# interface_smd.net
KiCad netlist of a schematic drawn in EAGLE
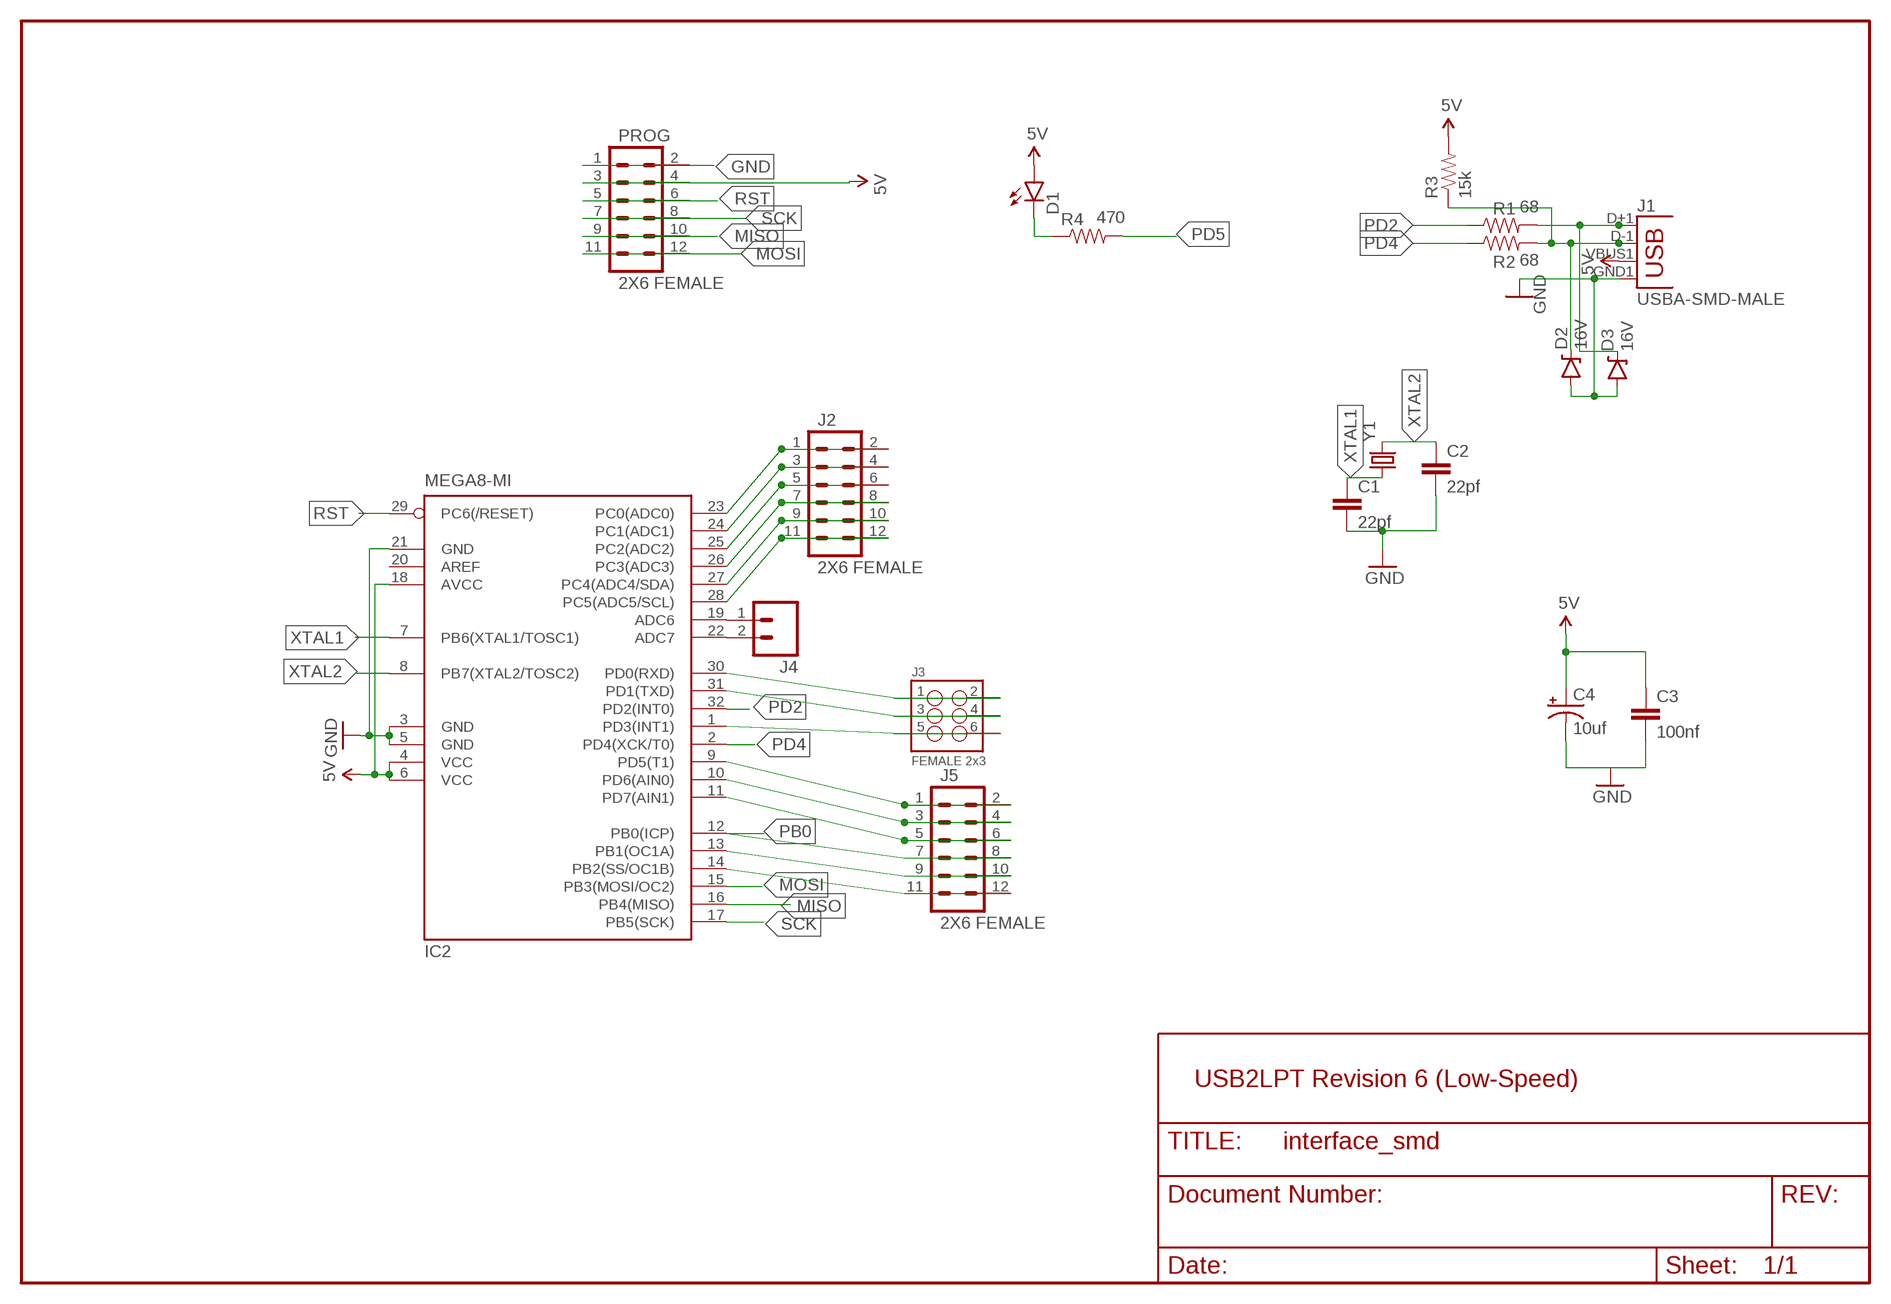
[diagram p0: schematic, sheet 1]

(export (version "E")
  (design (tool "Eeschema 10.0.6"))
  (components
    (comp (ref "C1")
      (value "22pf")
      (footprint "eagle-import:1206")
      (libsource (lib "eagle-import") (part "CAP1206"))
    )
    (comp (ref "C2")
      (value "22pf")
      (footprint "eagle-import:1206")
      (libsource (lib "eagle-import") (part "CAP1206"))
    )
    (comp (ref "C3")
      (value "100nf")
      (footprint "eagle-import:1206")
      (libsource (lib "eagle-import") (part "CAP1206"))
    )
    (comp (ref "C4")
      (value "10uf")
      (footprint "eagle-import:EIA3216")
      (libsource (lib "eagle-import") (part "CAP_POL1206"))
    )
    (comp (ref "D1")
      (value "LED1206")
      (footprint "eagle-import:LED-1206")
      (libsource (lib "eagle-import") (part "LED1206"))
    )
    (comp (ref "D2")
      (value "16V")
      (footprint "eagle-import:SOD-123")
      (libsource (lib "eagle-import") (part "DIODE-ZENER16V"))
    )
    (comp (ref "D3")
      (value "16V")
      (footprint "eagle-import:SOD-123")
      (libsource (lib "eagle-import") (part "DIODE-ZENER16V"))
    )
    (comp (ref "IC2")
      (value "MEGA8-MI")
      (footprint "eagle-import:MLF32")
      (fields (field (name "MPN") "ATMEGA88PA-MU"))
      (libsource (lib "eagle-import") (part "MEGA8-MI"))
    )
    (comp (ref "J1")
      (value "USBA-SMD-MALE")
      (footprint "eagle-import:USB-A-SMT-MALE")
      (libsource (lib "eagle-import") (part "USBA-SMD-MALE"))
    )
    (comp (ref "J2")
      (value "2X6 FEMALE")
      (footprint "eagle-import:2X6")
      (libsource (lib "eagle-import") (part "M06X2PTH_FEMALE"))
    )
    (comp (ref "J3")
      (value "FEMALE 2x3")
      (footprint "eagle-import:2X3")
      (libsource (lib "eagle-import") (part "M03X2FEMALE"))
    )
    (comp (ref "J4")
      (value "M02PTH")
      (footprint "eagle-import:1X02")
      (libsource (lib "eagle-import") (part "M02PTH"))
    )
    (comp (ref "J5")
      (value "2X6 FEMALE")
      (footprint "eagle-import:2X6")
      (libsource (lib "eagle-import") (part "M06X2PTH_FEMALE"))
    )
    (comp (ref "PROG")
      (value "2X6 FEMALE")
      (footprint "eagle-import:2X6")
      (libsource (lib "eagle-import") (part "M06X2PTH_FEMALE"))
    )
    (comp (ref "R1")
      (value "68")
      (footprint "eagle-import:1206")
      (libsource (lib "eagle-import") (part "RESISTOR1206"))
    )
    (comp (ref "R2")
      (value "68")
      (footprint "eagle-import:1206")
      (libsource (lib "eagle-import") (part "RESISTOR1206"))
    )
    (comp (ref "R3")
      (value "15k")
      (footprint "eagle-import:1206")
      (libsource (lib "eagle-import") (part "RESISTOR1206"))
    )
    (comp (ref "R4")
      (value "470")
      (footprint "eagle-import:1206")
      (libsource (lib "eagle-import") (part "RESISTOR1206"))
    )
    (comp (ref "Y1")
      (value "CRYSTAL10.5X4.8")
      (footprint "eagle-import:CRYSTAL-SMD-10.5X4.8-2PIN")
      (libsource (lib "eagle-import") (part "CRYSTAL10.5X4.8"))
    )
  )
  (nets
    (net (code "1") (name "5V") (class "Default")
      (node (ref "C3") (pin "1") (pinfunction "1_1") (pintype "passive"))
      (node (ref "C4") (pin "A") (pinfunction "+_A") (pintype "passive"))
      (node (ref "D1") (pin "A") (pinfunction "A_A") (pintype "passive"))
      (node (ref "IC2") (pin "18") (pinfunction "AVCC_18") (pintype "power_in"))
      (node (ref "IC2") (pin "4") (pinfunction "VCC_4") (pintype "power_in"))
      (node (ref "IC2") (pin "6") (pinfunction "VCC_6") (pintype "power_in"))
      (node (ref "J1") (pin "VBUS1") (pinfunction "VBUS_VBUS1") (pintype "bidirectional"))
      (node (ref "PROG") (pin "3") (pinfunction "3_3") (pintype "passive"))
      (node (ref "PROG") (pin "4") (pinfunction "4_4") (pintype "passive"))
      (node (ref "R3") (pin "2") (pinfunction "2_2") (pintype "passive"))
    )
    (net (code "2") (name "GND") (class "Default")
      (node (ref "C1") (pin "2") (pinfunction "2_2") (pintype "passive"))
      (node (ref "C2") (pin "2") (pinfunction "2_2") (pintype "passive"))
      (node (ref "C3") (pin "2") (pinfunction "2_2") (pintype "passive"))
      (node (ref "C4") (pin "C") (pinfunction "-_C") (pintype "passive"))
      (node (ref "D2") (pin "A") (pinfunction "A_A") (pintype "passive"))
      (node (ref "D3") (pin "A") (pinfunction "A_A") (pintype "passive"))
      (node (ref "IC2") (pin "21") (pinfunction "GND_21") (pintype "power_in"))
      (node (ref "IC2") (pin "3") (pinfunction "GND_3") (pintype "power_in"))
      (node (ref "IC2") (pin "5") (pinfunction "GND_5") (pintype "power_in"))
      (node (ref "J1") (pin "GND1") (pinfunction "GND_GND1") (pintype "bidirectional"))
      (node (ref "PROG") (pin "1") (pinfunction "1_1") (pintype "passive"))
      (node (ref "PROG") (pin "2") (pinfunction "2_2") (pintype "passive"))
    )
    (net (code "3") (name "MISO") (class "Default")
      (node (ref "IC2") (pin "16") (pinfunction "PB4(MISO)_16") (pintype "bidirectional"))
      (node (ref "PROG") (pin "10") (pinfunction "10_10") (pintype "passive"))
      (node (ref "PROG") (pin "9") (pinfunction "9_9") (pintype "passive"))
    )
    (net (code "4") (name "MOSI") (class "Default")
      (node (ref "IC2") (pin "15") (pinfunction "PB3(MOSI/OC2)_15") (pintype "bidirectional"))
      (node (ref "PROG") (pin "11") (pinfunction "11_11") (pintype "passive"))
      (node (ref "PROG") (pin "12") (pinfunction "12_12") (pintype "passive"))
    )
    (net (code "5") (name "Net-(D1-PadC)") (class "Default")
      (node (ref "D1") (pin "C") (pinfunction "C_C") (pintype "passive"))
      (node (ref "R4") (pin "1") (pinfunction "1_1") (pintype "passive"))
    )
    (net (code "6") (name "Net-(IC2-ADC6)") (class "Default")
      (node (ref "IC2") (pin "19") (pinfunction "ADC6_19") (pintype "bidirectional"))
      (node (ref "J4") (pin "1") (pinfunction "1_1") (pintype "passive"))
    )
    (net (code "7") (name "Net-(IC2-ADC7)") (class "Default")
      (node (ref "IC2") (pin "22") (pinfunction "ADC7_22") (pintype "bidirectional"))
      (node (ref "J4") (pin "2") (pinfunction "2_2") (pintype "passive"))
    )
    (net (code "8") (name "Net-(IC2-PB1(OC1A))") (class "Default")
      (node (ref "IC2") (pin "13") (pinfunction "PB1(OC1A)_13") (pintype "bidirectional"))
      (node (ref "J5") (pin "10") (pinfunction "10_10") (pintype "passive"))
      (node (ref "J5") (pin "9") (pinfunction "9_9") (pintype "passive"))
    )
    (net (code "9") (name "Net-(IC2-PB2(SS{slash}OC1B))") (class "Default")
      (node (ref "IC2") (pin "14") (pinfunction "PB2(SS/OC1B)_14") (pintype "bidirectional"))
      (node (ref "J5") (pin "11") (pinfunction "11_11") (pintype "passive"))
      (node (ref "J5") (pin "12") (pinfunction "12_12") (pintype "passive"))
    )
    (net (code "10") (name "Net-(IC2-PC0(ADC0))") (class "Default")
      (node (ref "IC2") (pin "23") (pinfunction "PC0(ADC0)_23") (pintype "bidirectional"))
      (node (ref "J2") (pin "1") (pinfunction "1_1") (pintype "passive"))
      (node (ref "J2") (pin "2") (pinfunction "2_2") (pintype "passive"))
    )
    (net (code "11") (name "Net-(IC2-PC1(ADC1))") (class "Default")
      (node (ref "IC2") (pin "24") (pinfunction "PC1(ADC1)_24") (pintype "bidirectional"))
      (node (ref "J2") (pin "3") (pinfunction "3_3") (pintype "passive"))
      (node (ref "J2") (pin "4") (pinfunction "4_4") (pintype "passive"))
    )
    (net (code "12") (name "Net-(IC2-PC2(ADC2))") (class "Default")
      (node (ref "IC2") (pin "25") (pinfunction "PC2(ADC2)_25") (pintype "bidirectional"))
      (node (ref "J2") (pin "5") (pinfunction "5_5") (pintype "passive"))
      (node (ref "J2") (pin "6") (pinfunction "6_6") (pintype "passive"))
    )
    (net (code "13") (name "Net-(IC2-PC3(ADC3))") (class "Default")
      (node (ref "IC2") (pin "26") (pinfunction "PC3(ADC3)_26") (pintype "bidirectional"))
      (node (ref "J2") (pin "7") (pinfunction "7_7") (pintype "passive"))
      (node (ref "J2") (pin "8") (pinfunction "8_8") (pintype "passive"))
    )
    (net (code "14") (name "Net-(IC2-PC4(ADC4{slash}SDA))") (class "Default")
      (node (ref "IC2") (pin "27") (pinfunction "PC4(ADC4/SDA)_27") (pintype "bidirectional"))
      (node (ref "J2") (pin "10") (pinfunction "10_10") (pintype "passive"))
      (node (ref "J2") (pin "9") (pinfunction "9_9") (pintype "passive"))
    )
    (net (code "15") (name "Net-(IC2-PC5(ADC5{slash}SCL))") (class "Default")
      (node (ref "IC2") (pin "28") (pinfunction "PC5(ADC5/SCL)_28") (pintype "bidirectional"))
      (node (ref "J2") (pin "11") (pinfunction "11_11") (pintype "passive"))
      (node (ref "J2") (pin "12") (pinfunction "12_12") (pintype "passive"))
    )
    (net (code "16") (name "Net-(IC2-PD0(RXD))") (class "Default")
      (node (ref "IC2") (pin "30") (pinfunction "PD0(RXD)_30") (pintype "bidirectional"))
      (node (ref "J3") (pin "1") (pinfunction "1_1") (pintype "bidirectional"))
      (node (ref "J3") (pin "2") (pinfunction "2_2") (pintype "bidirectional"))
    )
    (net (code "17") (name "Net-(IC2-PD1(TXD))") (class "Default")
      (node (ref "IC2") (pin "31") (pinfunction "PD1(TXD)_31") (pintype "bidirectional"))
      (node (ref "J3") (pin "3") (pinfunction "3_3") (pintype "bidirectional"))
      (node (ref "J3") (pin "4") (pinfunction "4_4") (pintype "bidirectional"))
    )
    (net (code "18") (name "Net-(IC2-PD3(INT1))") (class "Default")
      (node (ref "IC2") (pin "1") (pinfunction "PD3(INT1)_1") (pintype "bidirectional"))
      (node (ref "J3") (pin "5") (pinfunction "5_5") (pintype "bidirectional"))
      (node (ref "J3") (pin "6") (pinfunction "6_6") (pintype "bidirectional"))
    )
    (net (code "19") (name "Net-(IC2-PD6(AIN0))") (class "Default")
      (node (ref "IC2") (pin "10") (pinfunction "PD6(AIN0)_10") (pintype "bidirectional"))
      (node (ref "J5") (pin "3") (pinfunction "3_3") (pintype "passive"))
      (node (ref "J5") (pin "4") (pinfunction "4_4") (pintype "passive"))
    )
    (net (code "20") (name "Net-(IC2-PD7(AIN1))") (class "Default")
      (node (ref "IC2") (pin "11") (pinfunction "PD7(AIN1)_11") (pintype "bidirectional"))
      (node (ref "J5") (pin "5") (pinfunction "5_5") (pintype "passive"))
      (node (ref "J5") (pin "6") (pinfunction "6_6") (pintype "passive"))
    )
    (net (code "21") (name "Net-(J1-D+)") (class "Default")
      (node (ref "D3") (pin "C") (pinfunction "C_C") (pintype "passive"))
      (node (ref "J1") (pin "D+1") (pinfunction "D+_D+1") (pintype "bidirectional"))
      (node (ref "R1") (pin "2") (pinfunction "2_2") (pintype "passive"))
    )
    (net (code "22") (name "Net-(J1-D-)") (class "Default")
      (node (ref "D2") (pin "C") (pinfunction "C_C") (pintype "passive"))
      (node (ref "J1") (pin "D-1") (pinfunction "D-_D-1") (pintype "bidirectional"))
      (node (ref "R2") (pin "2") (pinfunction "2_2") (pintype "passive"))
      (node (ref "R3") (pin "1") (pinfunction "1_1") (pintype "passive"))
    )
    (net (code "23") (name "PB0") (class "Default")
      (node (ref "IC2") (pin "12") (pinfunction "PB0(ICP)_12") (pintype "bidirectional"))
      (node (ref "J5") (pin "7") (pinfunction "7_7") (pintype "passive"))
      (node (ref "J5") (pin "8") (pinfunction "8_8") (pintype "passive"))
    )
    (net (code "24") (name "PD2") (class "Default")
      (node (ref "IC2") (pin "32") (pinfunction "PD2(INT0)_32") (pintype "bidirectional"))
      (node (ref "R1") (pin "1") (pinfunction "1_1") (pintype "passive"))
    )
    (net (code "25") (name "PD4") (class "Default")
      (node (ref "IC2") (pin "2") (pinfunction "PD4(XCK/T0)_2") (pintype "bidirectional"))
      (node (ref "R2") (pin "1") (pinfunction "1_1") (pintype "passive"))
    )
    (net (code "26") (name "PD5") (class "Default")
      (node (ref "IC2") (pin "9") (pinfunction "PD5(T1)_9") (pintype "bidirectional"))
      (node (ref "J5") (pin "1") (pinfunction "1_1") (pintype "passive"))
      (node (ref "J5") (pin "2") (pinfunction "2_2") (pintype "passive"))
      (node (ref "R4") (pin "2") (pinfunction "2_2") (pintype "passive"))
    )
    (net (code "27") (name "RST") (class "Default")
      (node (ref "IC2") (pin "29") (pinfunction "PC6(/RESET)_29") (pintype "bidirectional"))
      (node (ref "PROG") (pin "5") (pinfunction "5_5") (pintype "passive"))
      (node (ref "PROG") (pin "6") (pinfunction "6_6") (pintype "passive"))
    )
    (net (code "28") (name "SCK") (class "Default")
      (node (ref "IC2") (pin "17") (pinfunction "PB5(SCK)_17") (pintype "bidirectional"))
      (node (ref "PROG") (pin "7") (pinfunction "7_7") (pintype "passive"))
      (node (ref "PROG") (pin "8") (pinfunction "8_8") (pintype "passive"))
    )
    (net (code "29") (name "XTAL1") (class "Default")
      (node (ref "C1") (pin "1") (pinfunction "1_1") (pintype "passive"))
      (node (ref "IC2") (pin "7") (pinfunction "PB6(XTAL1/TOSC1)_7") (pintype "bidirectional"))
      (node (ref "Y1") (pin "P$1") (pinfunction "1_P$1") (pintype "passive"))
    )
    (net (code "30") (name "XTAL2") (class "Default")
      (node (ref "C2") (pin "1") (pinfunction "1_1") (pintype "passive"))
      (node (ref "IC2") (pin "8") (pinfunction "PB7(XTAL2/TOSC2)_8") (pintype "bidirectional"))
      (node (ref "Y1") (pin "P$2") (pinfunction "2_P$2") (pintype "passive"))
    )
    (net (code "31") (name "unconnected-(IC2-AREF-Pad20)") (class "Default")
      (node (ref "IC2") (pin "20") (pinfunction "AREF_20") (pintype "passive"))
    )
  )
)
